# Utility_Shield_1_4.net
KiCad netlist of a schematic drawn in EAGLE
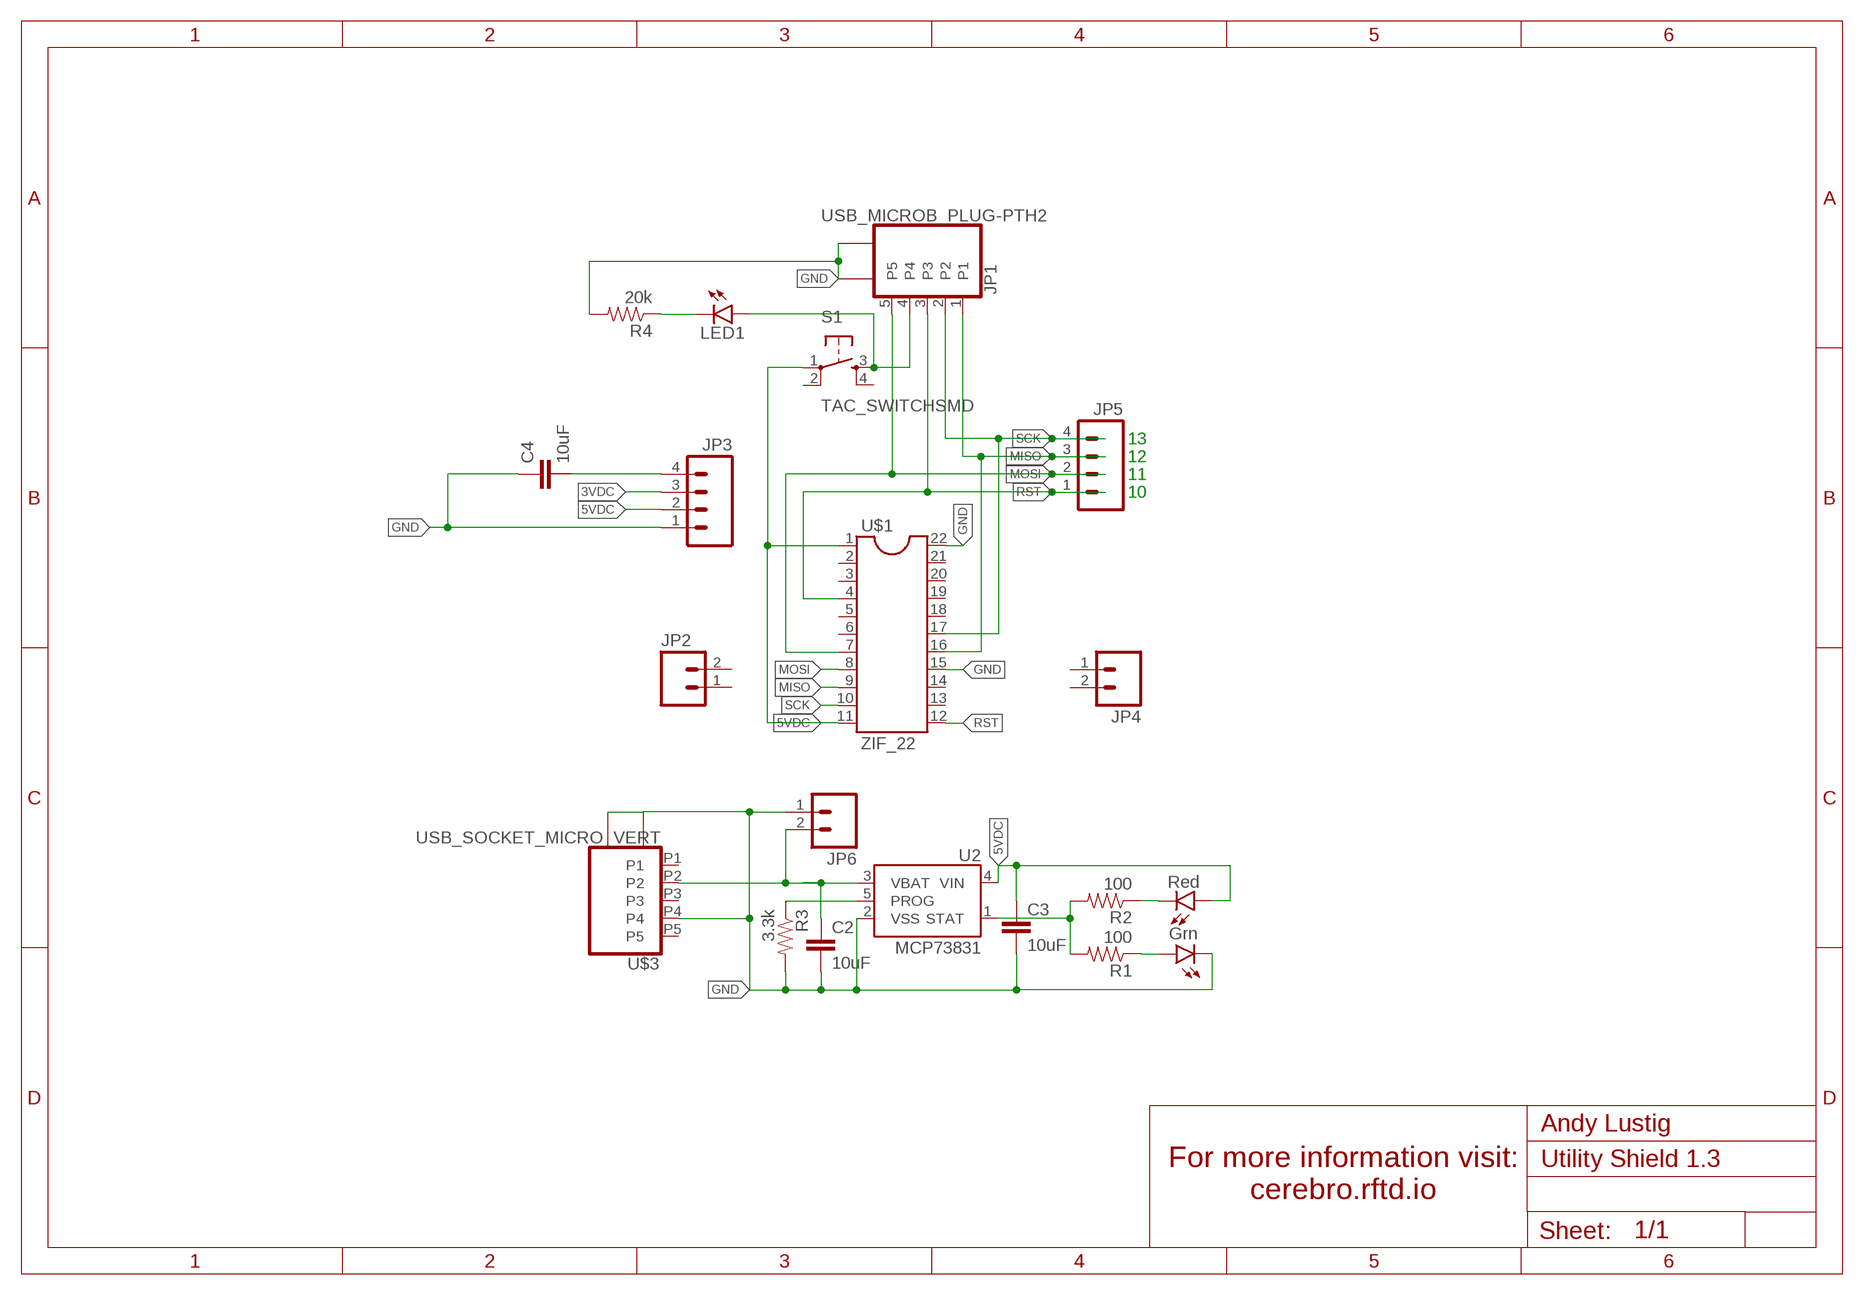
[diagram p0: schematic, sheet 1]

(export (version "E")
  (design (tool "Eeschema 10.0.6"))
  (components
    (comp (ref "C2")
      (value "10uF")
      (footprint "eagle-import:0805-CAP")
      (libsource (lib "eagle-import") (part "1.0UF-25V-+80/-20(0805){dblquote}"))
    )
    (comp (ref "C3")
      (value "10uF")
      (footprint "eagle-import:0805-CAP")
      (libsource (lib "eagle-import") (part "1.0UF-25V-+80/-20(0805){dblquote}"))
    )
    (comp (ref "C4")
      (value "10uF")
      (footprint "eagle-import:0805-CAP")
      (libsource (lib "eagle-import") (part "1.0UF-25V-+80/-20(0805){dblquote}"))
    )
    (comp (ref "JP1")
      (value "USB_MICROB_PLUG-PTH2")
      (footprint "eagle-import:MICRO-B-TH")
      (libsource (lib "eagle-import") (part "USB_MICROB_PLUG-PTH2"))
    )
    (comp (ref "JP2")
      (value "M02PTH")
      (footprint "eagle-import:1X02")
      (libsource (lib "eagle-import") (part "M02PTH"))
    )
    (comp (ref "JP3")
      (value "M04PTH")
      (footprint "eagle-import:1X04")
      (libsource (lib "eagle-import") (part "M04PTH"))
    )
    (comp (ref "JP4")
      (value "M02PTH")
      (footprint "eagle-import:1X02")
      (libsource (lib "eagle-import") (part "M02PTH"))
    )
    (comp (ref "JP5")
      (value "M04PTH")
      (footprint "eagle-import:1X04")
      (libsource (lib "eagle-import") (part "M04PTH"))
    )
    (comp (ref "JP6")
      (value "M02-JST-2-PTH-NO_SILK")
      (footprint "eagle-import:JST-2-PTH-NS")
      (libsource (lib "eagle-import") (part "M02-JST-2-PTH-NO_SILK"))
    )
    (comp (ref "LED1")
      (value "LED0603")
      (footprint "eagle-import:LED-0603")
      (libsource (lib "eagle-import") (part "LED0603"))
    )
    (comp (ref "R1")
      (value "100")
      (footprint "eagle-import:0805")
      (libsource (lib "eagle-import") (part "RESISTOR0805-RES"))
    )
    (comp (ref "R2")
      (value "100")
      (footprint "eagle-import:0805")
      (libsource (lib "eagle-import") (part "RESISTOR0805-RES"))
    )
    (comp (ref "R3")
      (value "3.3k")
      (footprint "eagle-import:0805")
      (libsource (lib "eagle-import") (part "RESISTOR0805-RES"))
    )
    (comp (ref "R4")
      (value "20k")
      (footprint "eagle-import:0805")
      (libsource (lib "eagle-import") (part "RESISTOR0805-RES"))
    )
    (comp (ref "S1")
      (value "TAC_SWITCHSMD")
      (footprint "eagle-import:TACTILE-SWITCH-SMD")
      (libsource (lib "eagle-import") (part "TAC_SWITCHSMD"))
    )
    (comp (ref "U$1")
      (value "ZIF_22")
      (footprint "eagle-import:ZIF_22")
      (libsource (lib "eagle-import") (part "ZIF_22"))
    )
    (comp (ref "U$2")
      (value "LED_DUAL")
      (footprint "eagle-import:LED_DUAL")
      (libsource (lib "eagle-import") (part "LED_DUAL"))
    )
    (comp (ref "U$3")
      (value "USB_SOCKET_MICRO_VERT")
      (footprint "eagle-import:USB_VERT_MICRO_SMD")
      (libsource (lib "eagle-import") (part "USB_SOCKET_MICRO_VERT"))
    )
    (comp (ref "U2")
      (value "MCP73831")
      (footprint "eagle-import:SOT23-5")
      (libsource (lib "eagle-import") (part "MCP73831"))
    )
  )
  (nets
    (net (code "1") (name "3VDC") (class "Default")
      (node (ref "JP3") (pin "3") (pinfunction "3_3") (pintype "passive"))
    )
    (net (code "2") (name "5VDC") (class "Default")
      (node (ref "C3") (pin "1") (pinfunction "1_1") (pintype "passive"))
      (node (ref "JP3") (pin "2") (pinfunction "2_2") (pintype "passive"))
      (node (ref "S1") (pin "1") (pinfunction "1_1") (pintype "passive"))
      (node (ref "U$1") (pin "1") (pinfunction "1_1") (pintype "passive"))
      (node (ref "U$1") (pin "11") (pinfunction "11_11") (pintype "passive"))
      (node (ref "U$2") (pin "RA") (pinfunction "RA_RA") (pintype "passive"))
      (node (ref "U2") (pin "4") (pinfunction "VIN_4") (pintype "power_in"))
    )
    (net (code "3") (name "GND") (class "Default")
      (node (ref "C2") (pin "2") (pinfunction "2_2") (pintype "passive"))
      (node (ref "C3") (pin "2") (pinfunction "2_2") (pintype "passive"))
      (node (ref "C4") (pin "1") (pinfunction "1_1") (pintype "passive"))
      (node (ref "JP1") (pin "P$1") (pinfunction "P$1_P$1") (pintype "bidirectional"))
      (node (ref "JP1") (pin "P$2") (pinfunction "P$2_P$2") (pintype "bidirectional"))
      (node (ref "JP3") (pin "1") (pinfunction "1_1") (pintype "passive"))
      (node (ref "JP6") (pin "1") (pinfunction "1_1") (pintype "passive"))
      (node (ref "R3") (pin "2") (pinfunction "2_2") (pintype "passive"))
      (node (ref "R4") (pin "2") (pinfunction "2_2") (pintype "passive"))
      (node (ref "U$1") (pin "15") (pinfunction "15_15") (pintype "passive"))
      (node (ref "U$1") (pin "22") (pinfunction "22_22") (pintype "passive"))
      (node (ref "U$2") (pin "GC") (pinfunction "GC_GC") (pintype "passive"))
      (node (ref "U$3") (pin "P$1") (pinfunction "P$1_P$1") (pintype "bidirectional"))
      (node (ref "U$3") (pin "P$2") (pinfunction "P$2_P$2") (pintype "bidirectional"))
      (node (ref "U$3") (pin "P$3") (pinfunction "P$2_P$3") (pintype "bidirectional"))
      (node (ref "U$3") (pin "P4") (pinfunction "P4_P4") (pintype "bidirectional"))
      (node (ref "U2") (pin "2") (pinfunction "VSS_2") (pintype "power_in"))
    )
    (net (code "4") (name "MISO") (class "Default")
      (node (ref "JP1") (pin "1") (pinfunction "P1_1") (pintype "bidirectional"))
      (node (ref "JP5") (pin "3") (pinfunction "3_3") (pintype "passive"))
      (node (ref "U$1") (pin "16") (pinfunction "16_16") (pintype "passive"))
      (node (ref "U$1") (pin "9") (pinfunction "9_9") (pintype "passive"))
    )
    (net (code "5") (name "MOSI") (class "Default")
      (node (ref "JP1") (pin "5") (pinfunction "P5_5") (pintype "bidirectional"))
      (node (ref "JP5") (pin "2") (pinfunction "2_2") (pintype "passive"))
      (node (ref "U$1") (pin "7") (pinfunction "7_7") (pintype "passive"))
      (node (ref "U$1") (pin "8") (pinfunction "8_8") (pintype "passive"))
    )
    (net (code "6") (name "Net-(C4-Pad2)") (class "Default")
      (node (ref "C4") (pin "2") (pinfunction "2_2") (pintype "passive"))
      (node (ref "JP3") (pin "4") (pinfunction "4_4") (pintype "passive"))
    )
    (net (code "7") (name "Net-(JP1-P4)") (class "Default")
      (node (ref "JP1") (pin "4") (pinfunction "P4_4") (pintype "bidirectional"))
      (node (ref "LED1") (pin "A") (pinfunction "A_A") (pintype "passive"))
      (node (ref "S1") (pin "3") (pinfunction "3_3") (pintype "passive"))
    )
    (net (code "8") (name "Net-(LED1-PadC)") (class "Default")
      (node (ref "LED1") (pin "C") (pinfunction "C_C") (pintype "passive"))
      (node (ref "R4") (pin "1") (pinfunction "1_1") (pintype "passive"))
    )
    (net (code "9") (name "Net-(R1-Pad1)") (class "Default")
      (node (ref "R1") (pin "1") (pinfunction "1_1") (pintype "passive"))
      (node (ref "U$2") (pin "GA") (pinfunction "GA_GA") (pintype "passive"))
    )
    (net (code "10") (name "Net-(R2-Pad1)") (class "Default")
      (node (ref "R2") (pin "1") (pinfunction "1_1") (pintype "passive"))
      (node (ref "U$2") (pin "RC") (pinfunction "RC_RC") (pintype "passive"))
    )
    (net (code "11") (name "Net-(U2-PROG)") (class "Default")
      (node (ref "R3") (pin "1") (pinfunction "1_1") (pintype "passive"))
      (node (ref "U2") (pin "5") (pinfunction "PROG_5") (pintype "input"))
    )
    (net (code "12") (name "Net-(U2-STAT)") (class "Default")
      (node (ref "R1") (pin "2") (pinfunction "2_2") (pintype "passive"))
      (node (ref "R2") (pin "2") (pinfunction "2_2") (pintype "passive"))
      (node (ref "U2") (pin "1") (pinfunction "STAT_1") (pintype "output"))
    )
    (net (code "13") (name "Net-(U2-VBAT)") (class "Default")
      (node (ref "C2") (pin "1") (pinfunction "1_1") (pintype "passive"))
      (node (ref "JP6") (pin "2") (pinfunction "2_2") (pintype "passive"))
      (node (ref "U$3") (pin "P2") (pinfunction "P2_P2") (pintype "bidirectional"))
      (node (ref "U2") (pin "3") (pinfunction "VBAT_3") (pintype "power_in"))
    )
    (net (code "14") (name "RST") (class "Default")
      (node (ref "JP1") (pin "3") (pinfunction "P3_3") (pintype "bidirectional"))
      (node (ref "JP5") (pin "1") (pinfunction "1_1") (pintype "passive"))
      (node (ref "U$1") (pin "12") (pinfunction "12_12") (pintype "passive"))
      (node (ref "U$1") (pin "4") (pinfunction "4_4") (pintype "passive"))
    )
    (net (code "15") (name "SCK") (class "Default")
      (node (ref "JP1") (pin "2") (pinfunction "P2_2") (pintype "bidirectional"))
      (node (ref "JP5") (pin "4") (pinfunction "4_4") (pintype "passive"))
      (node (ref "U$1") (pin "10") (pinfunction "10_10") (pintype "passive"))
      (node (ref "U$1") (pin "17") (pinfunction "17_17") (pintype "passive"))
    )
    (net (code "16") (name "unconnected-(JP2-Pad1)") (class "Default")
      (node (ref "JP2") (pin "1") (pinfunction "1_1") (pintype "passive"))
    )
    (net (code "17") (name "unconnected-(JP2-Pad2)") (class "Default")
      (node (ref "JP2") (pin "2") (pinfunction "2_2") (pintype "passive"))
    )
    (net (code "18") (name "unconnected-(JP4-Pad1)") (class "Default")
      (node (ref "JP4") (pin "1") (pinfunction "1_1") (pintype "passive"))
    )
    (net (code "19") (name "unconnected-(JP4-Pad2)") (class "Default")
      (node (ref "JP4") (pin "2") (pinfunction "2_2") (pintype "passive"))
    )
    (net (code "20") (name "unconnected-(S1-Pad2)") (class "Default")
      (node (ref "S1") (pin "2") (pinfunction "2_2") (pintype "passive"))
    )
    (net (code "21") (name "unconnected-(S1-Pad4)") (class "Default")
      (node (ref "S1") (pin "4") (pinfunction "4_4") (pintype "passive"))
    )
    (net (code "22") (name "unconnected-(U$1-Pad2)") (class "Default")
      (node (ref "U$1") (pin "2") (pinfunction "2_2") (pintype "passive"))
    )
    (net (code "23") (name "unconnected-(U$1-Pad3)") (class "Default")
      (node (ref "U$1") (pin "3") (pinfunction "3_3") (pintype "passive"))
    )
    (net (code "24") (name "unconnected-(U$1-Pad5)") (class "Default")
      (node (ref "U$1") (pin "5") (pinfunction "5_5") (pintype "passive"))
    )
    (net (code "25") (name "unconnected-(U$1-Pad6)") (class "Default")
      (node (ref "U$1") (pin "6") (pinfunction "6_6") (pintype "passive"))
    )
    (net (code "26") (name "unconnected-(U$1-Pad13)") (class "Default")
      (node (ref "U$1") (pin "13") (pinfunction "13_13") (pintype "passive"))
    )
    (net (code "27") (name "unconnected-(U$1-Pad14)") (class "Default")
      (node (ref "U$1") (pin "14") (pinfunction "14_14") (pintype "passive"))
    )
    (net (code "28") (name "unconnected-(U$1-Pad18)") (class "Default")
      (node (ref "U$1") (pin "18") (pinfunction "18_18") (pintype "passive"))
    )
    (net (code "29") (name "unconnected-(U$1-Pad19)") (class "Default")
      (node (ref "U$1") (pin "19") (pinfunction "19_19") (pintype "passive"))
    )
    (net (code "30") (name "unconnected-(U$1-Pad20)") (class "Default")
      (node (ref "U$1") (pin "20") (pinfunction "20_20") (pintype "passive"))
    )
    (net (code "31") (name "unconnected-(U$1-Pad21)") (class "Default")
      (node (ref "U$1") (pin "21") (pinfunction "21_21") (pintype "passive"))
    )
    (net (code "32") (name "unconnected-(U$3-PadP1)") (class "Default")
      (node (ref "U$3") (pin "P1") (pinfunction "P1_P1") (pintype "bidirectional"))
    )
    (net (code "33") (name "unconnected-(U$3-PadP3)") (class "Default")
      (node (ref "U$3") (pin "P3") (pinfunction "P3_P3") (pintype "bidirectional"))
    )
    (net (code "34") (name "unconnected-(U$3-PadP5)") (class "Default")
      (node (ref "U$3") (pin "P5") (pinfunction "P5_P5") (pintype "bidirectional"))
    )
  )
)
